# Sensor_PCB_M2.net
KiCad netlist of a schematic drawn in EAGLE
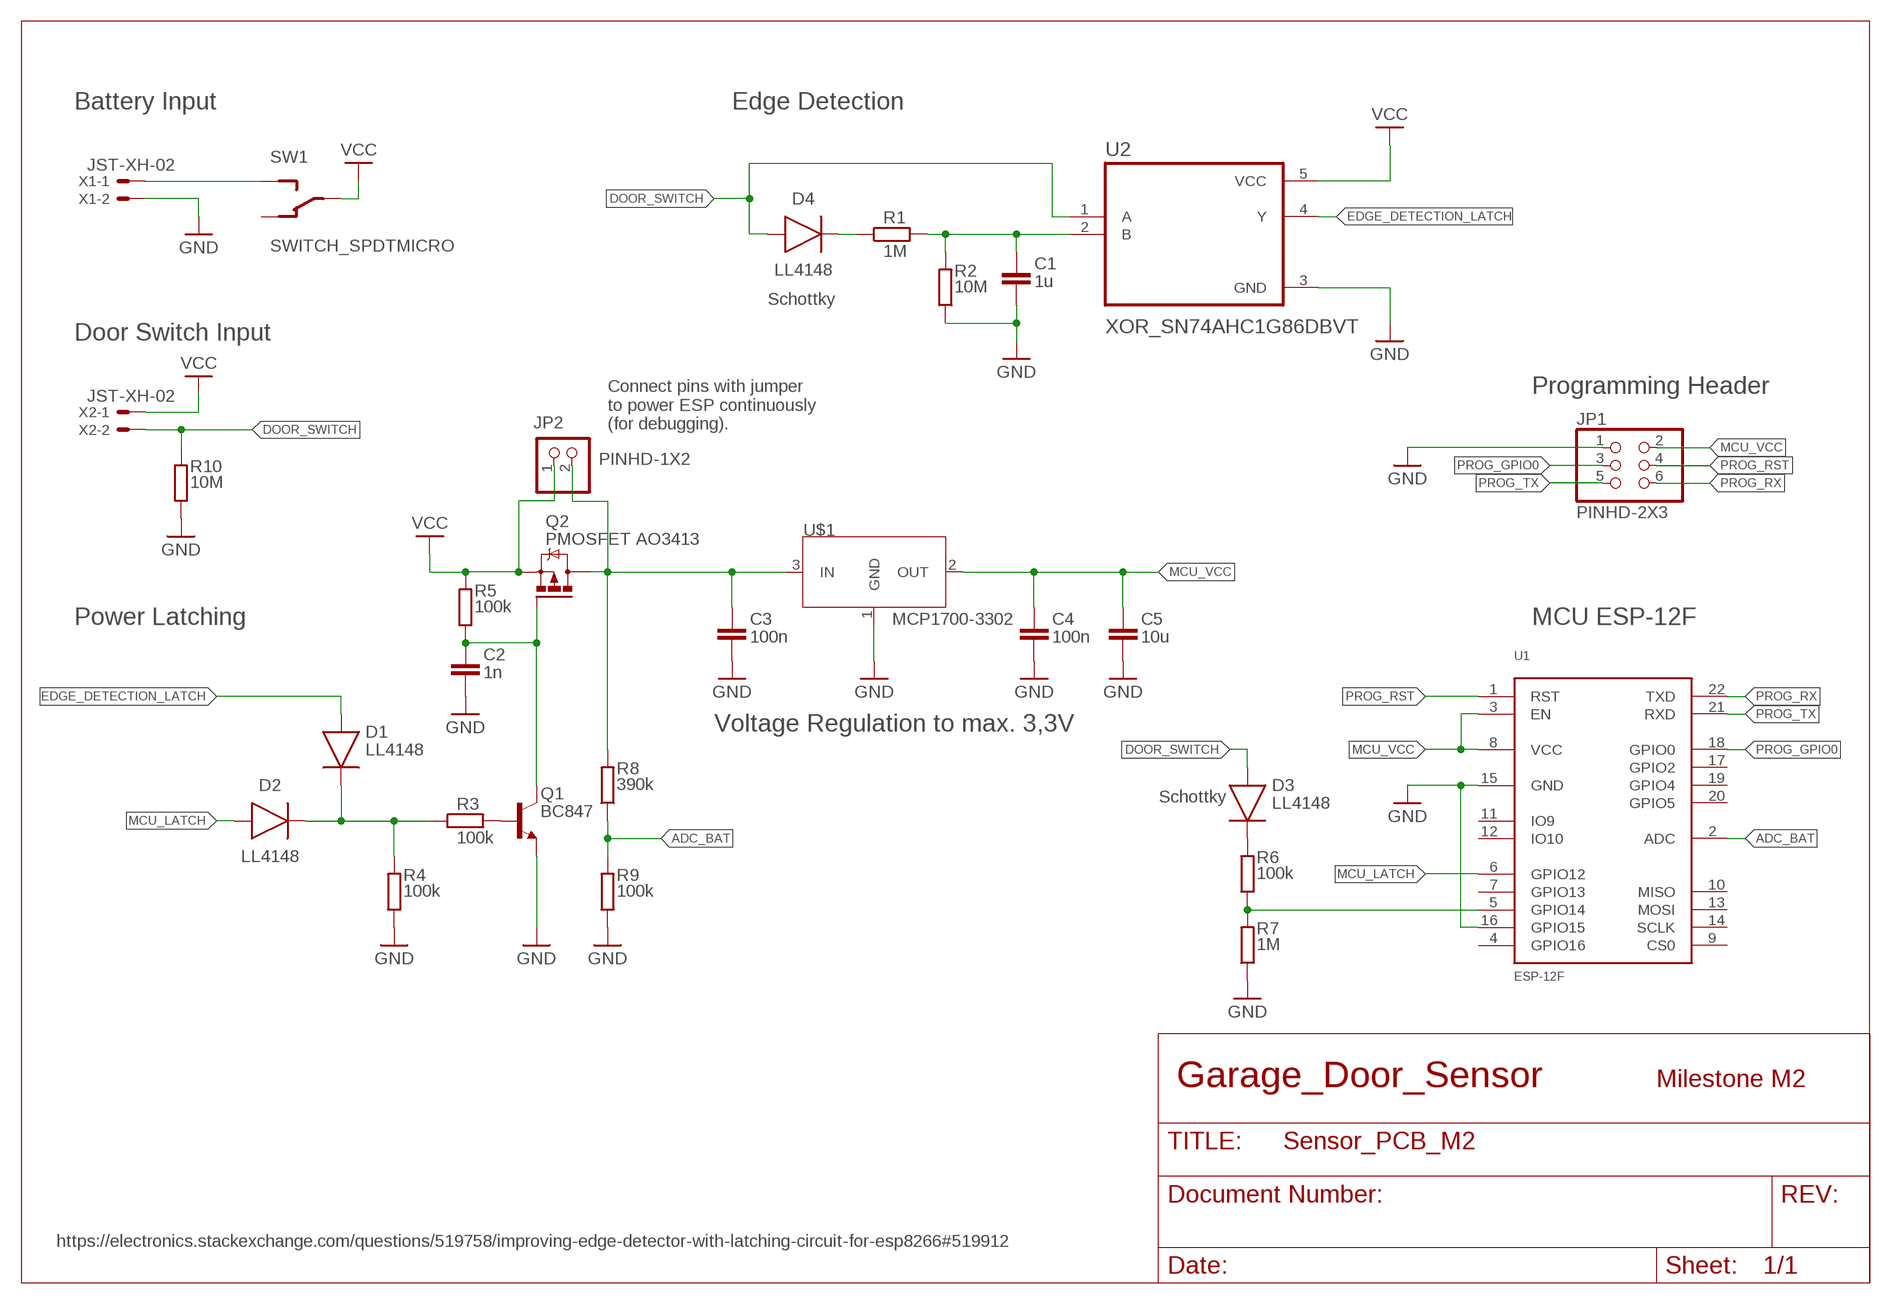
[diagram p0: schematic, sheet 1]

(export (version "E")
  (design (tool "Eeschema 10.0.6"))
  (components
    (comp (ref "C1")
      (value "1u")
      (footprint "eagle-import:CAPC2012X110")
      (libsource (lib "eagle-import") (part "CCHIP-0805(2012-METRIC)_"))
    )
    (comp (ref "C2")
      (value "1n")
      (footprint "eagle-import:CAPC2012X110")
      (libsource (lib "eagle-import") (part "CCHIP-0805(2012-METRIC)_"))
    )
    (comp (ref "C3")
      (value "100n")
      (footprint "eagle-import:CAPC2012X110")
      (libsource (lib "eagle-import") (part "CCHIP-0805(2012-METRIC)_"))
    )
    (comp (ref "C4")
      (value "100n")
      (footprint "eagle-import:CAPC2012X110")
      (libsource (lib "eagle-import") (part "CCHIP-0805(2012-METRIC)_"))
    )
    (comp (ref "C5")
      (value "10u")
      (footprint "eagle-import:CAPC2012X110")
      (libsource (lib "eagle-import") (part "CCHIP-0805(2012-METRIC)_"))
    )
    (comp (ref "D1")
      (value "LL4148")
      (footprint "eagle-import:DIOMELF3516")
      (fields (field (name "MANUFACTURER") "ON Semiconductor "))
      (libsource (lib "eagle-import") (part "DIODE__SOD-80LL4148"))
    )
    (comp (ref "D2")
      (value "LL4148")
      (footprint "eagle-import:DIOMELF3516")
      (fields (field (name "MANUFACTURER") "ON Semiconductor "))
      (libsource (lib "eagle-import") (part "DIODE__SOD-80LL4148"))
    )
    (comp (ref "D3")
      (value "LL4148")
      (footprint "eagle-import:DIOMELF3516")
      (fields (field (name "MANUFACTURER") "ON Semiconductor "))
      (libsource (lib "eagle-import") (part "DIODE__SOD-80LL4148"))
    )
    (comp (ref "D4")
      (value "LL4148")
      (footprint "eagle-import:DIOMELF3516")
      (fields (field (name "MANUFACTURER") "ON Semiconductor "))
      (libsource (lib "eagle-import") (part "DIODE__SOD-80LL4148"))
    )
    (comp (ref "JP1")
      (value "PINHD-2X3")
      (footprint "eagle-import:2X03")
      (fields (field (name "MANUFACTURER") "Generic"))
      (libsource (lib "eagle-import") (part "PINHD-2X3"))
    )
    (comp (ref "JP2")
      (value "PINHD-1X2")
      (footprint "eagle-import:1X02")
      (fields (field (name "MANUFACTURER") "Generic"))
      (libsource (lib "eagle-import") (part "PINHD-1X2"))
    )
    (comp (ref "Q1")
      (value "BC847")
      (footprint "eagle-import:SOT95P237X112-3N")
      (libsource (lib "eagle-import") (part "NPNSOT23-BEC_"))
    )
    (comp (ref "Q2")
      (value "PMOSFET AO3413")
      (footprint "eagle-import:SOT23")
      (libsource (lib "eagle-import") (part "PMOSFETSOT23-GSD_"))
    )
    (comp (ref "R1")
      (value "1M")
      (footprint "eagle-import:R0805")
      (libsource (lib "eagle-import") (part "R-EU_R0805"))
    )
    (comp (ref "R2")
      (value "10M")
      (footprint "eagle-import:R0805")
      (libsource (lib "eagle-import") (part "R-EU_R0805"))
    )
    (comp (ref "R3")
      (value "100k")
      (footprint "eagle-import:R0805")
      (libsource (lib "eagle-import") (part "R-EU_R0805"))
    )
    (comp (ref "R4")
      (value "100k")
      (footprint "eagle-import:R0805")
      (libsource (lib "eagle-import") (part "R-EU_R0805"))
    )
    (comp (ref "R5")
      (value "100k")
      (footprint "eagle-import:R0805")
      (libsource (lib "eagle-import") (part "R-EU_R0805"))
    )
    (comp (ref "R6")
      (value "100k")
      (footprint "eagle-import:R0805")
      (libsource (lib "eagle-import") (part "R-EU_R0805"))
    )
    (comp (ref "R7")
      (value "1M")
      (footprint "eagle-import:R0805")
      (libsource (lib "eagle-import") (part "R-EU_R0805"))
    )
    (comp (ref "R8")
      (value "390k")
      (footprint "eagle-import:R0805")
      (libsource (lib "eagle-import") (part "R-EU_R0805"))
    )
    (comp (ref "R9")
      (value "100k")
      (footprint "eagle-import:R0805")
      (libsource (lib "eagle-import") (part "R-EU_R0805"))
    )
    (comp (ref "R10")
      (value "10M")
      (footprint "eagle-import:R0805")
      (libsource (lib "eagle-import") (part "R-EU_R0805"))
    )
    (comp (ref "SW1")
      (value "SWITCH_SPDTMICRO")
      (footprint "eagle-import:MICROSWITCH_SPDT")
      (libsource (lib "eagle-import") (part "SWITCH_SPDTMICRO"))
    )
    (comp (ref "U$1")
      (value "MCP1700-3302")
      (footprint "eagle-import:SOT23")
      (libsource (lib "eagle-import") (part "MCP1700-3302"))
    )
    (comp (ref "U1")
      (value "ESP-12F")
      (footprint "eagle-import:ESP-12F")
      (fields (field (name "MF") "AI-Thinker"))
      (libsource (lib "eagle-import") (part "ESP-12F"))
    )
    (comp (ref "U2")
      (value "XOR_SN74AHC1G86DBVT")
      (footprint "eagle-import:SOT95P280X145-5N")
      (fields (field (name "MF") "Texas Instruments") (field (name "MP") "SN74AHC1G86DBVT"))
      (libsource (lib "eagle-import") (part "SN74AHC1G86DBVT"))
    )
    (comp (ref "X1")
      (value "JST-XH-02")
      (footprint "eagle-import:JST-XH-02-PACKAGE-LONG-PAD")
      (libsource (lib "eagle-import") (part "JST-XH-02-PIN-LONG-PAD"))
    )
    (comp (ref "X2")
      (value "JST-XH-02")
      (footprint "eagle-import:JST-XH-02-PACKAGE-LONG-PAD")
      (libsource (lib "eagle-import") (part "JST-XH-02-PIN-LONG-PAD"))
    )
  )
  (nets
    (net (code "1") (name "ADC_BAT") (class "Default")
      (node (ref "R8") (pin "1") (pinfunction "1_1") (pintype "passive"))
      (node (ref "R9") (pin "2") (pinfunction "2_2") (pintype "passive"))
      (node (ref "U1") (pin "2") (pinfunction "ADC_2") (pintype "bidirectional"))
    )
    (net (code "2") (name "DOOR_SWITCH") (class "Default")
      (node (ref "D3") (pin "2") (pinfunction "A_2") (pintype "passive"))
      (node (ref "D4") (pin "2") (pinfunction "A_2") (pintype "passive"))
      (node (ref "R10") (pin "2") (pinfunction "2_2") (pintype "passive"))
      (node (ref "U2") (pin "1") (pinfunction "A_1") (pintype "input"))
      (node (ref "X2") (pin "2") (pinfunction "S_2") (pintype "passive"))
    )
    (net (code "3") (name "EDGE_DETECTION_LATCH") (class "Default")
      (node (ref "D1") (pin "2") (pinfunction "A_2") (pintype "passive"))
      (node (ref "U2") (pin "4") (pinfunction "Y_4") (pintype "output"))
    )
    (net (code "4") (name "GND") (class "Default")
      (node (ref "C1") (pin "2") (pinfunction "2_2") (pintype "passive"))
      (node (ref "C2") (pin "2") (pinfunction "2_2") (pintype "passive"))
      (node (ref "C3") (pin "2") (pinfunction "2_2") (pintype "passive"))
      (node (ref "C4") (pin "2") (pinfunction "2_2") (pintype "passive"))
      (node (ref "C5") (pin "2") (pinfunction "2_2") (pintype "passive"))
      (node (ref "JP1") (pin "1") (pinfunction "1_1") (pintype "passive"))
      (node (ref "Q1") (pin "2") (pinfunction "E_2") (pintype "passive"))
      (node (ref "R10") (pin "1") (pinfunction "1_1") (pintype "passive"))
      (node (ref "R2") (pin "1") (pinfunction "1_1") (pintype "passive"))
      (node (ref "R4") (pin "1") (pinfunction "1_1") (pintype "passive"))
      (node (ref "R7") (pin "1") (pinfunction "1_1") (pintype "passive"))
      (node (ref "R9") (pin "1") (pinfunction "1_1") (pintype "passive"))
      (node (ref "U$1") (pin "1") (pinfunction "GND_1") (pintype "bidirectional"))
      (node (ref "U1") (pin "15") (pinfunction "GND_15") (pintype "bidirectional"))
      (node (ref "U1") (pin "16") (pinfunction "GPIO15_16") (pintype "bidirectional"))
      (node (ref "U2") (pin "3") (pinfunction "GND_3") (pintype "power_in"))
      (node (ref "X1") (pin "2") (pinfunction "S_2") (pintype "passive"))
    )
    (net (code "5") (name "MCU_LATCH") (class "Default")
      (node (ref "D2") (pin "2") (pinfunction "A_2") (pintype "passive"))
      (node (ref "U1") (pin "6") (pinfunction "GPIO12_6") (pintype "bidirectional"))
    )
    (net (code "6") (name "MCU_VCC") (class "Default")
      (node (ref "C4") (pin "1") (pinfunction "1_1") (pintype "passive"))
      (node (ref "C5") (pin "1") (pinfunction "1_1") (pintype "passive"))
      (node (ref "JP1") (pin "2") (pinfunction "2_2") (pintype "passive"))
      (node (ref "U$1") (pin "2") (pinfunction "OUT_2") (pintype "bidirectional"))
      (node (ref "U1") (pin "3") (pinfunction "EN_3") (pintype "bidirectional"))
      (node (ref "U1") (pin "8") (pinfunction "VCC_8") (pintype "bidirectional"))
    )
    (net (code "7") (name "Net-(D1-C)") (class "Default")
      (node (ref "D1") (pin "1") (pinfunction "C_1") (pintype "passive"))
      (node (ref "D2") (pin "1") (pinfunction "C_1") (pintype "passive"))
      (node (ref "R3") (pin "1") (pinfunction "1_1") (pintype "passive"))
      (node (ref "R4") (pin "2") (pinfunction "2_2") (pintype "passive"))
    )
    (net (code "8") (name "Net-(D3-C)") (class "Default")
      (node (ref "D3") (pin "1") (pinfunction "C_1") (pintype "passive"))
      (node (ref "R6") (pin "2") (pinfunction "2_2") (pintype "passive"))
    )
    (net (code "9") (name "Net-(D4-C)") (class "Default")
      (node (ref "D4") (pin "1") (pinfunction "C_1") (pintype "passive"))
      (node (ref "R1") (pin "1") (pinfunction "1_1") (pintype "passive"))
    )
    (net (code "10") (name "Net-(Q1-B)") (class "Default")
      (node (ref "Q1") (pin "1") (pinfunction "B_1") (pintype "passive"))
      (node (ref "R3") (pin "2") (pinfunction "2_2") (pintype "passive"))
    )
    (net (code "11") (name "Net-(Q1-C)") (class "Default")
      (node (ref "C2") (pin "1") (pinfunction "1_1") (pintype "passive"))
      (node (ref "Q1") (pin "3") (pinfunction "C_3") (pintype "passive"))
      (node (ref "Q2") (pin "1") (pinfunction "G_1") (pintype "passive"))
      (node (ref "R5") (pin "1") (pinfunction "1_1") (pintype "passive"))
    )
    (net (code "12") (name "Net-(Q2-D)") (class "Default")
      (node (ref "C3") (pin "1") (pinfunction "1_1") (pintype "passive"))
      (node (ref "JP2") (pin "2") (pinfunction "2_2") (pintype "passive"))
      (node (ref "Q2") (pin "3") (pinfunction "D_3") (pintype "passive"))
      (node (ref "R8") (pin "2") (pinfunction "2_2") (pintype "passive"))
      (node (ref "U$1") (pin "3") (pinfunction "IN_3") (pintype "bidirectional"))
    )
    (net (code "13") (name "Net-(U1-GPIO14)") (class "Default")
      (node (ref "R6") (pin "1") (pinfunction "1_1") (pintype "passive"))
      (node (ref "R7") (pin "2") (pinfunction "2_2") (pintype "passive"))
      (node (ref "U1") (pin "5") (pinfunction "GPIO14_5") (pintype "bidirectional"))
    )
    (net (code "14") (name "Net-(U2-B)") (class "Default")
      (node (ref "C1") (pin "1") (pinfunction "1_1") (pintype "passive"))
      (node (ref "R1") (pin "2") (pinfunction "2_2") (pintype "passive"))
      (node (ref "R2") (pin "2") (pinfunction "2_2") (pintype "passive"))
      (node (ref "U2") (pin "2") (pinfunction "B_2") (pintype "input"))
    )
    (net (code "15") (name "Net-(X1A-S)") (class "Default")
      (node (ref "SW1") (pin "P$1") (pinfunction "P$1_P$1") (pintype "passive"))
      (node (ref "X1") (pin "1") (pinfunction "S_1") (pintype "passive"))
    )
    (net (code "16") (name "PROG_GPIO0") (class "Default")
      (node (ref "JP1") (pin "3") (pinfunction "3_3") (pintype "passive"))
      (node (ref "U1") (pin "18") (pinfunction "GPIO0_18") (pintype "bidirectional"))
    )
    (net (code "17") (name "PROG_RST") (class "Default")
      (node (ref "JP1") (pin "4") (pinfunction "4_4") (pintype "passive"))
      (node (ref "U1") (pin "1") (pinfunction "RST_1") (pintype "bidirectional"))
    )
    (net (code "18") (name "PROG_RX") (class "Default")
      (node (ref "JP1") (pin "6") (pinfunction "6_6") (pintype "passive"))
      (node (ref "U1") (pin "22") (pinfunction "TXD_22") (pintype "bidirectional"))
    )
    (net (code "19") (name "PROG_TX") (class "Default")
      (node (ref "JP1") (pin "5") (pinfunction "5_5") (pintype "passive"))
      (node (ref "U1") (pin "21") (pinfunction "RXD_21") (pintype "bidirectional"))
    )
    (net (code "20") (name "VCC") (class "Default")
      (node (ref "JP2") (pin "1") (pinfunction "1_1") (pintype "passive"))
      (node (ref "Q2") (pin "2") (pinfunction "S_2") (pintype "passive"))
      (node (ref "R5") (pin "2") (pinfunction "2_2") (pintype "passive"))
      (node (ref "SW1") (pin "P$2") (pinfunction "P$2_P$2") (pintype "passive"))
      (node (ref "U2") (pin "5") (pinfunction "VCC_5") (pintype "power_in"))
      (node (ref "X2") (pin "1") (pinfunction "S_1") (pintype "passive"))
    )
    (net (code "21") (name "unconnected-(SW1-PadP$3)") (class "Default")
      (node (ref "SW1") (pin "P$3") (pinfunction "P$3_P$3") (pintype "passive"))
    )
    (net (code "22") (name "unconnected-(U1-CS0-Pad9)") (class "Default")
      (node (ref "U1") (pin "9") (pinfunction "CS0_9") (pintype "bidirectional"))
    )
    (net (code "23") (name "unconnected-(U1-GPIO2-Pad17)") (class "Default")
      (node (ref "U1") (pin "17") (pinfunction "GPIO2_17") (pintype "bidirectional"))
    )
    (net (code "24") (name "unconnected-(U1-GPIO4-Pad19)") (class "Default")
      (node (ref "U1") (pin "19") (pinfunction "GPIO4_19") (pintype "bidirectional"))
    )
    (net (code "25") (name "unconnected-(U1-GPIO5-Pad20)") (class "Default")
      (node (ref "U1") (pin "20") (pinfunction "GPIO5_20") (pintype "bidirectional"))
    )
    (net (code "26") (name "unconnected-(U1-GPIO13-Pad7)") (class "Default")
      (node (ref "U1") (pin "7") (pinfunction "GPIO13_7") (pintype "bidirectional"))
    )
    (net (code "27") (name "unconnected-(U1-GPIO16-Pad4)") (class "Default")
      (node (ref "U1") (pin "4") (pinfunction "GPIO16_4") (pintype "bidirectional"))
    )
    (net (code "28") (name "unconnected-(U1-IO9-Pad11)") (class "Default")
      (node (ref "U1") (pin "11") (pinfunction "IO9_11") (pintype "bidirectional"))
    )
    (net (code "29") (name "unconnected-(U1-IO10-Pad12)") (class "Default")
      (node (ref "U1") (pin "12") (pinfunction "IO10_12") (pintype "bidirectional"))
    )
    (net (code "30") (name "unconnected-(U1-MISO-Pad10)") (class "Default")
      (node (ref "U1") (pin "10") (pinfunction "MISO_10") (pintype "bidirectional"))
    )
    (net (code "31") (name "unconnected-(U1-MOSI-Pad13)") (class "Default")
      (node (ref "U1") (pin "13") (pinfunction "MOSI_13") (pintype "bidirectional"))
    )
    (net (code "32") (name "unconnected-(U1-SCLK-Pad14)") (class "Default")
      (node (ref "U1") (pin "14") (pinfunction "SCLK_14") (pintype "bidirectional"))
    )
  )
)
